# System_PMU_for_RK3399.net
KiCad netlist of a schematic drawn in Altium Designer
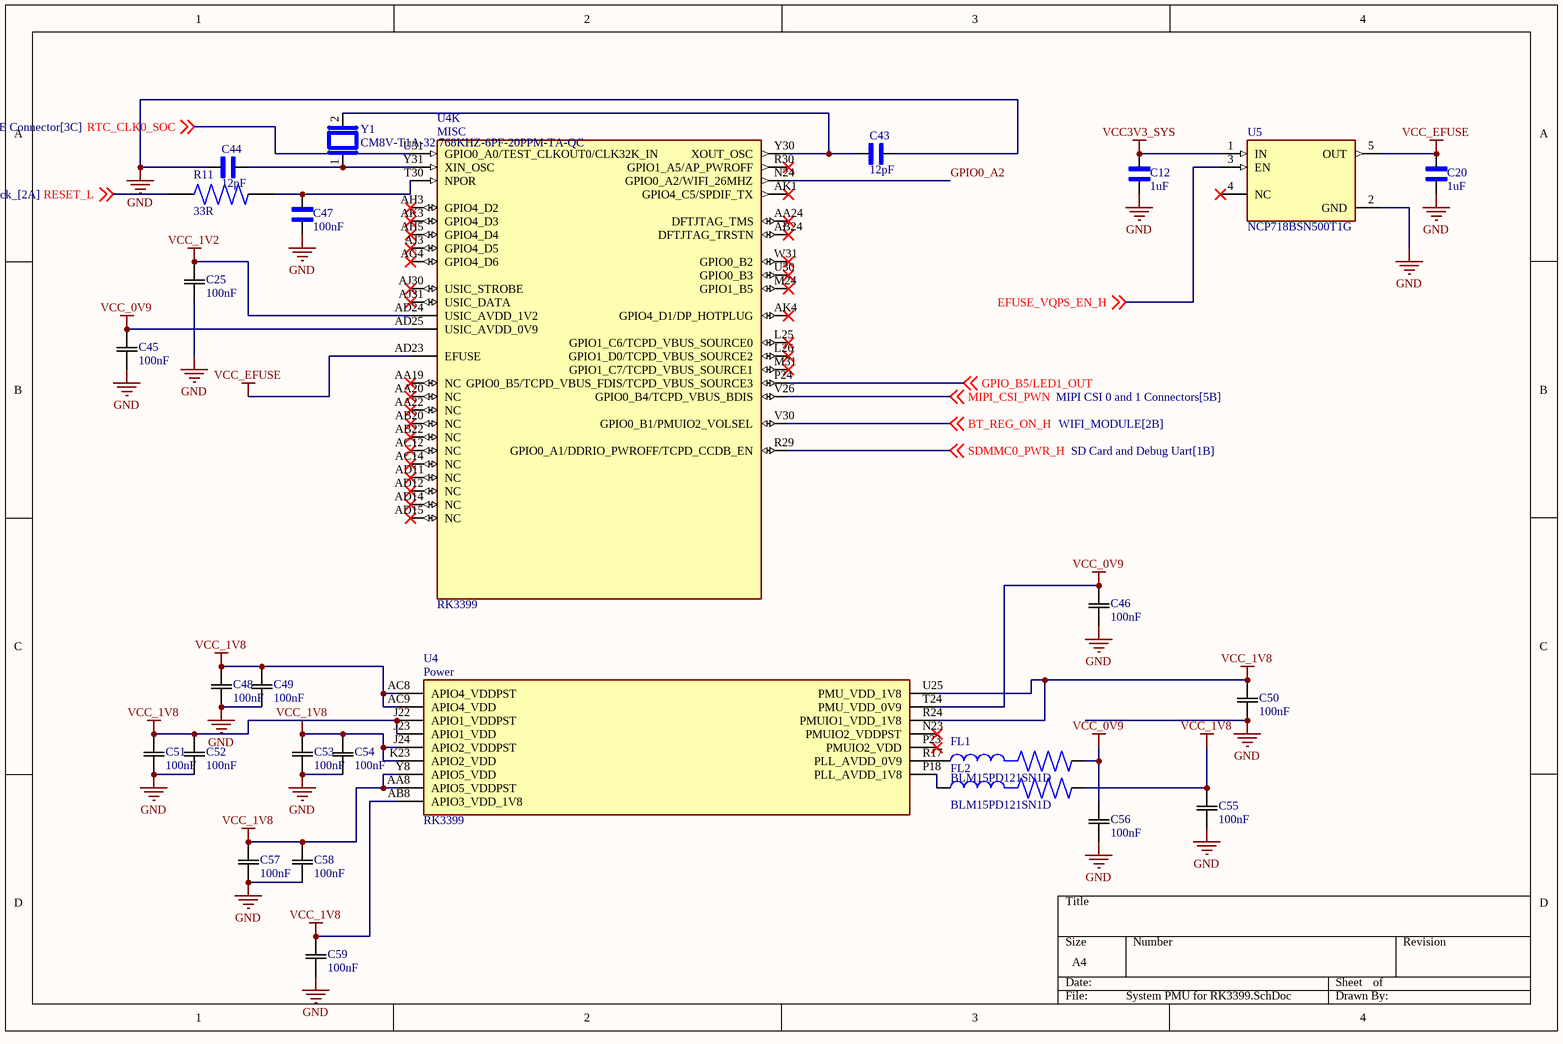
[diagram p0: System PMU for RK3399.SchDoc]

(export (version "E")
  (design (tool "Eeschema 10.0.6"))
  (components
    (comp (ref "C12")
      (value "1uF")
      (footprint "CAPC1005X56N")
      (description "1 ÂµF Â±10% 10V Ceramic Capacitor X5R 0402 (1005 Metric)")
      (fields (field (name "MF") "AVX") (field (name "MP") "0402ZD105KAT4A"))
      (libsource (lib "0402ZD105KAT4A") (part "0402ZD105KAT4A"))
    )
    (comp (ref "C20")
      (value "1uF")
      (footprint "CAPC1005X56N")
      (description "1 ÂµF Â±10% 10V Ceramic Capacitor X5R 0402 (1005 Metric)")
      (fields (field (name "MF") "AVX") (field (name "MP") "0402ZD105KAT4A"))
      (libsource (lib "0402ZD105KAT4A") (part "0402ZD105KAT4A"))
    )
    (comp (ref "C25")
      (value "100nF")
      (footprint "CAP_1005_TDK")
      (description "Description")
      (fields
        (field (name "MANUFACTURER_PART_NUMBER") "C1005X7R1H104M050BB")
        (field (name "COPYRIGHT") "Copyright (C) 2025 Ultra Librarian. All rights reserved.")
      )
      (libsource (lib "C1005X7R1H104M050BB") (part "C1005X7R1H104M050BB"))
    )
    (comp (ref "C43")
      (value "12pF")
      (footprint "CAPC1608X90")
      (description "12 pF Thin Film Capacitor 50 V 0603 (1608 Metric)")
      (fields (field (name "MF") "AVX") (field (name "MP") "06035J120FBSTR"))
      (libsource (lib "06035J120FBSTR") (part "06035J120FBSTR"))
    )
    (comp (ref "C44")
      (value "12pF")
      (footprint "CAPC0603X33N")
      (description "Cap Ceramic 12pF 25V C0G 2% Pad SMD 0201 125Â°C T/R")
      (fields (field (name "MF") "KYOCERA AVX Components") (field (name "MP") "02013A120GAT2A"))
      (libsource (lib "02013A120GAT2A") (part "02013A120GAT2A"))
    )
    (comp (ref "C45")
      (value "100nF")
      (footprint "CAP_1005_TDK")
      (description "Description")
      (fields
        (field (name "MANUFACTURER_PART_NUMBER") "C1005X7R1H104M050BB")
        (field (name "COPYRIGHT") "Copyright (C) 2025 Ultra Librarian. All rights reserved.")
      )
      (libsource (lib "C1005X7R1H104M050BB") (part "C1005X7R1H104M050BB"))
    )
    (comp (ref "C46")
      (value "100nF")
      (footprint "CAP_1005_TDK")
      (description "Description")
      (fields
        (field (name "MANUFACTURER_PART_NUMBER") "C1005X7R1H104M050BB")
        (field (name "COPYRIGHT") "Copyright (C) 2025 Ultra Librarian. All rights reserved.")
      )
      (libsource (lib "C1005X7R1H104M050BB") (part "C1005X7R1H104M050BB"))
    )
    (comp (ref "C47")
      (value "100nF")
      (footprint "CAPC2012X90N")
      (description "Capacitor: ceramic; MLCC; 100nF; 25V; X7R; Â±10%; SMD; 0805")
      (fields (field (name "MF") "Vishay Vitramon") (field (name "MP") "VJ0805Y104KXXCW1BC"))
      (libsource (lib "VJ0805Y104KXXCW1BC") (part "VJ0805Y104KXXCW1BC"))
    )
    (comp (ref "C48")
      (value "100nF")
      (footprint "CAP_1005_TDK")
      (description "Description")
      (fields
        (field (name "MANUFACTURER_PART_NUMBER") "C1005X7R1H104M050BB")
        (field (name "COPYRIGHT") "Copyright (C) 2025 Ultra Librarian. All rights reserved.")
      )
      (libsource (lib "C1005X7R1H104M050BB") (part "C1005X7R1H104M050BB"))
    )
    (comp (ref "C49")
      (value "100nF")
      (footprint "CAP_1005_TDK")
      (description "Description")
      (fields
        (field (name "MANUFACTURER_PART_NUMBER") "C1005X7R1H104M050BB")
        (field (name "COPYRIGHT") "Copyright (C) 2025 Ultra Librarian. All rights reserved.")
      )
      (libsource (lib "C1005X7R1H104M050BB") (part "C1005X7R1H104M050BB"))
    )
    (comp (ref "C50")
      (value "100nF")
      (footprint "CAP_1005_TDK")
      (description "Description")
      (fields
        (field (name "MANUFACTURER_PART_NUMBER") "C1005X7R1H104M050BB")
        (field (name "COPYRIGHT") "Copyright (C) 2025 Ultra Librarian. All rights reserved.")
      )
      (libsource (lib "C1005X7R1H104M050BB") (part "C1005X7R1H104M050BB"))
    )
    (comp (ref "C51")
      (value "100nF")
      (footprint "CAP_1005_TDK")
      (description "Description")
      (fields
        (field (name "MANUFACTURER_PART_NUMBER") "C1005X7R1H104M050BB")
        (field (name "COPYRIGHT") "Copyright (C) 2025 Ultra Librarian. All rights reserved.")
      )
      (libsource (lib "C1005X7R1H104M050BB") (part "C1005X7R1H104M050BB"))
    )
    (comp (ref "C52")
      (value "100nF")
      (footprint "CAP_1005_TDK")
      (description "Description")
      (fields
        (field (name "MANUFACTURER_PART_NUMBER") "C1005X7R1H104M050BB")
        (field (name "COPYRIGHT") "Copyright (C) 2025 Ultra Librarian. All rights reserved.")
      )
      (libsource (lib "C1005X7R1H104M050BB") (part "C1005X7R1H104M050BB"))
    )
    (comp (ref "C53")
      (value "100nF")
      (footprint "CAP_1005_TDK")
      (description "Description")
      (fields
        (field (name "MANUFACTURER_PART_NUMBER") "C1005X7R1H104M050BB")
        (field (name "COPYRIGHT") "Copyright (C) 2025 Ultra Librarian. All rights reserved.")
      )
      (libsource (lib "C1005X7R1H104M050BB") (part "C1005X7R1H104M050BB"))
    )
    (comp (ref "C54")
      (value "100nF")
      (footprint "CAP_1005_TDK")
      (description "Description")
      (fields
        (field (name "MANUFACTURER_PART_NUMBER") "C1005X7R1H104M050BB")
        (field (name "COPYRIGHT") "Copyright (C) 2025 Ultra Librarian. All rights reserved.")
      )
      (libsource (lib "C1005X7R1H104M050BB") (part "C1005X7R1H104M050BB"))
    )
    (comp (ref "C55")
      (value "100nF")
      (footprint "CAP_1005_TDK")
      (description "Description")
      (fields
        (field (name "MANUFACTURER_PART_NUMBER") "C1005X7R1H104M050BB")
        (field (name "COPYRIGHT") "Copyright (C) 2025 Ultra Librarian. All rights reserved.")
      )
      (libsource (lib "C1005X7R1H104M050BB") (part "C1005X7R1H104M050BB"))
    )
    (comp (ref "C56")
      (value "100nF")
      (footprint "CAP_1005_TDK")
      (description "Description")
      (fields
        (field (name "MANUFACTURER_PART_NUMBER") "C1005X7R1H104M050BB")
        (field (name "COPYRIGHT") "Copyright (C) 2025 Ultra Librarian. All rights reserved.")
      )
      (libsource (lib "C1005X7R1H104M050BB") (part "C1005X7R1H104M050BB"))
    )
    (comp (ref "C57")
      (value "100nF")
      (footprint "CAP_1005_TDK")
      (description "Description")
      (fields
        (field (name "MANUFACTURER_PART_NUMBER") "C1005X7R1H104M050BB")
        (field (name "COPYRIGHT") "Copyright (C) 2025 Ultra Librarian. All rights reserved.")
      )
      (libsource (lib "C1005X7R1H104M050BB") (part "C1005X7R1H104M050BB"))
    )
    (comp (ref "C58")
      (value "100nF")
      (footprint "CAP_1005_TDK")
      (description "Description")
      (fields
        (field (name "MANUFACTURER_PART_NUMBER") "C1005X7R1H104M050BB")
        (field (name "COPYRIGHT") "Copyright (C) 2025 Ultra Librarian. All rights reserved.")
      )
      (libsource (lib "C1005X7R1H104M050BB") (part "C1005X7R1H104M050BB"))
    )
    (comp (ref "C59")
      (value "100nF")
      (footprint "CAP_1005_TDK")
      (description "Description")
      (fields
        (field (name "MANUFACTURER_PART_NUMBER") "C1005X7R1H104M050BB")
        (field (name "COPYRIGHT") "Copyright (C) 2025 Ultra Librarian. All rights reserved.")
      )
      (libsource (lib "C1005X7R1H104M050BB") (part "C1005X7R1H104M050BB"))
    )
    (comp (ref "FL1")
      (value "BLM15PD121SN1D")
      (footprint "BEADC1005X55N")
      (description "120 Ohms @ 100 MHz 1 Power Line Ferrite Bead 0402 (1005 Metric) 1.3A 90mOhm")
      (fields (field (name "MF") "Murata"))
      (libsource (lib "BLM15PD121SN1D") (part "BLM15PD121SN1D"))
    )
    (comp (ref "FL2")
      (value "BLM15PD121SN1D")
      (footprint "BEADC1005X55N")
      (description "120 Ohms @ 100 MHz 1 Power Line Ferrite Bead 0402 (1005 Metric) 1.3A 90mOhm")
      (fields (field (name "MF") "Murata"))
      (libsource (lib "BLM15PD121SN1D") (part "BLM15PD121SN1D"))
    )
    (comp (ref "R11")
      (value "33R")
      (footprint "RES_ERA6AHD330V")
      (fields (field (name "MP") "ERA6AHD330V"))
      (libsource (lib "ERA6AHD330V") (part "ERA6AHD330V"))
    )
    (comp (ref "U4")
      (value "RK3399")
      (footprint "BGA828C65P31X31_2100X2100X161N")
      (description "RK3399 ROCK Pi 4 Model A 2GB - ARMÂ® CortexÂ®-A53, CortexÂ®-A72 MPU Embedded Evaluation Board")
      (fields (field (name "MF") "Rockchip"))
      (libsource (lib "RK3399") (part "RK3399"))
    )
    (comp (ref "U5")
      (value "NCP718BSN500T1G")
      (footprint "SOT95P280X100-5N")
      (description "Linear Voltage Regulator IC Positive Fixed 1 Output 300mA TSOT-23-5")
      (fields (field (name "MF") "ON Semiconductor"))
      (libsource (lib "NCP718BSN500T1G") (part "NCP718BSN500T1G"))
    )
    (comp (ref "Y1")
      (value "CM8V-T1A-32.768KHZ-6PF-20PPM-TA-QC")
      (footprint "XTAL_CM8V-T1A-32.768KHZ-6PF-20PPM-TA-QC")
      (description "Tuning Fork Crystal 32.768kHz in SMD 1.2 x 2.0mm package")
      (fields (field (name "MF") "Micro Crystal") (field (name "MP") "CM8V-T1A-32.768kHz-6pF-20PPM-TA-QC"))
      (libsource (lib "CM8V-T1A-32.768KHZ-6PF-20PPM-TA-QC") (part "CM8V-T1A-32.768KHZ-6PF-20PPM-TA-QC"))
    )
  )
  (nets
    (net (code "1") (name "/GPIO0_A2") (class "Default")
      (node (ref "U4") (pin "N24") (pinfunction "GPIO0_A2/WIFI_26MHZ_N24") (pintype "output"))
    )
    (net (code "2") (name "BT_REG_ON_H") (class "Default")
      (node (ref "U4") (pin "V30") (pinfunction "GPIO0_B1/PMUIO2_VOLSEL_V30") (pintype "bidirectional"))
    )
    (net (code "3") (name "EFUSE_VQPS_EN_H") (class "Default")
      (node (ref "U5") (pin "3") (pinfunction "EN_3") (pintype "input"))
    )
    (net (code "4") (name "GND") (class "Default")
      (node (ref "C12") (pin "2") (pinfunction "2_2") (pintype "passive"))
      (node (ref "C20") (pin "2") (pinfunction "2_2") (pintype "passive"))
      (node (ref "C25") (pin "2") (pinfunction "2_2") (pintype "passive"))
      (node (ref "C43") (pin "1") (pinfunction "1_1") (pintype "passive"))
      (node (ref "C44") (pin "1") (pinfunction "1_1") (pintype "passive"))
      (node (ref "C45") (pin "2") (pinfunction "2_2") (pintype "passive"))
      (node (ref "C46") (pin "2") (pinfunction "2_2") (pintype "passive"))
      (node (ref "C47") (pin "2") (pinfunction "2_2") (pintype "passive"))
      (node (ref "C48") (pin "2") (pinfunction "2_2") (pintype "passive"))
      (node (ref "C49") (pin "2") (pinfunction "2_2") (pintype "passive"))
      (node (ref "C50") (pin "2") (pinfunction "2_2") (pintype "passive"))
      (node (ref "C51") (pin "2") (pinfunction "2_2") (pintype "passive"))
      (node (ref "C52") (pin "2") (pinfunction "2_2") (pintype "passive"))
      (node (ref "C53") (pin "2") (pinfunction "2_2") (pintype "passive"))
      (node (ref "C54") (pin "1") (pinfunction "1_1") (pintype "passive"))
      (node (ref "C55") (pin "2") (pinfunction "2_2") (pintype "passive"))
      (node (ref "C56") (pin "2") (pinfunction "2_2") (pintype "passive"))
      (node (ref "C57") (pin "2") (pinfunction "2_2") (pintype "passive"))
      (node (ref "C58") (pin "2") (pinfunction "2_2") (pintype "passive"))
      (node (ref "C59") (pin "2") (pinfunction "2_2") (pintype "passive"))
      (node (ref "U5") (pin "2") (pinfunction "GND_2") (pintype "power_in"))
    )
    (net (code "5") (name "GPIO_B5{slash}LED1_OUT") (class "Default")
      (node (ref "U4") (pin "P24") (pinfunction "GPIO0_B5/TCPD_VBUS_FDIS/TCPD_VBUS_SOURCE3_P24") (pintype "bidirectional"))
    )
    (net (code "6") (name "MIPI_CSI_PWN") (class "Default")
      (node (ref "U4") (pin "V26") (pinfunction "GPIO0_B4/TCPD_VBUS_BDIS_V26") (pintype "bidirectional"))
    )
    (net (code "7") (name "Net-(U4AC-PLL_AVDD_0V9)") (class "Default")
      (node (ref "FL1") (pin "1") (pinfunction "1_1") (pintype "passive"))
      (node (ref "U4") (pin "R17") (pinfunction "PLL_AVDD_0V9_R17") (pintype "power_in"))
    )
    (net (code "8") (name "Net-(U4AC-PLL_AVDD_1V8)") (class "Default")
      (node (ref "FL2") (pin "1") (pinfunction "1_1") (pintype "passive"))
      (node (ref "U4") (pin "P18") (pinfunction "PLL_AVDD_1V8_P18") (pintype "power_in"))
    )
    (net (code "9") (name "Net-(U4K-NPOR)") (class "Default")
      (node (ref "C47") (pin "1") (pinfunction "1_1") (pintype "passive"))
      (node (ref "R11") (pin "2") (pinfunction "2_2") (pintype "passive"))
      (node (ref "U4") (pin "T30") (pinfunction "NPOR_T30") (pintype "input"))
    )
    (net (code "10") (name "Net-(U4K-XIN_OSC)") (class "Default")
      (node (ref "C44") (pin "2") (pinfunction "2_2") (pintype "passive"))
      (node (ref "U4") (pin "Y31") (pinfunction "XIN_OSC_Y31") (pintype "input"))
      (node (ref "Y1") (pin "1") (pinfunction "1_1") (pintype "passive"))
    )
    (net (code "11") (name "Net-(U4K-XOUT_OSC)") (class "Default")
      (node (ref "C43") (pin "2") (pinfunction "2_2") (pintype "passive"))
      (node (ref "U4") (pin "Y30") (pinfunction "XOUT_OSC_Y30") (pintype "output"))
      (node (ref "Y1") (pin "2") (pinfunction "2_2") (pintype "passive"))
    )
    (net (code "12") (name "RESET_L") (class "Default")
      (node (ref "R11") (pin "1") (pinfunction "1_1") (pintype "passive"))
    )
    (net (code "13") (name "RTC_CLK0_SOC") (class "Default")
      (node (ref "U4") (pin "U31") (pinfunction "GPIO0_A0/TEST_CLKOUT0/CLK32K_IN_U31") (pintype "input"))
    )
    (net (code "14") (name "SDMMC0_PWR_H") (class "Default")
      (node (ref "U4") (pin "R29") (pinfunction "GPIO0_A1/DDRIO_PWROFF/TCPD_CCDB_EN_R29") (pintype "bidirectional"))
    )
    (net (code "15") (name "VCC3V3_SYS") (class "Default")
      (node (ref "C12") (pin "1") (pinfunction "1_1") (pintype "passive"))
      (node (ref "U5") (pin "1") (pinfunction "IN_1") (pintype "input"))
    )
    (net (code "16") (name "VCC_0V9") (class "Default")
      (node (ref "C45") (pin "1") (pinfunction "1_1") (pintype "passive"))
      (node (ref "C46") (pin "1") (pinfunction "1_1") (pintype "passive"))
      (node (ref "C56") (pin "1") (pinfunction "1_1") (pintype "passive"))
      (node (ref "FL1") (pin "2") (pinfunction "2_2") (pintype "passive"))
      (node (ref "U4") (pin "AD25") (pinfunction "USIC_AVDD_0V9_AD25") (pintype "power_in"))
      (node (ref "U4") (pin "T24") (pinfunction "PMU_VDD_0V9_T24") (pintype "power_in"))
    )
    (net (code "17") (name "VCC_1V2") (class "Default")
      (node (ref "C25") (pin "1") (pinfunction "1_1") (pintype "passive"))
      (node (ref "U4") (pin "AD24") (pinfunction "USIC_AVDD_1V2_AD24") (pintype "power_in"))
    )
    (net (code "18") (name "VCC_1V8") (class "Default")
      (node (ref "C48") (pin "1") (pinfunction "1_1") (pintype "passive"))
      (node (ref "C49") (pin "1") (pinfunction "1_1") (pintype "passive"))
      (node (ref "C50") (pin "1") (pinfunction "1_1") (pintype "passive"))
      (node (ref "C51") (pin "1") (pinfunction "1_1") (pintype "passive"))
      (node (ref "C52") (pin "1") (pinfunction "1_1") (pintype "passive"))
      (node (ref "C53") (pin "1") (pinfunction "1_1") (pintype "passive"))
      (node (ref "C54") (pin "2") (pinfunction "2_2") (pintype "passive"))
      (node (ref "C55") (pin "1") (pinfunction "1_1") (pintype "passive"))
      (node (ref "C57") (pin "1") (pinfunction "1_1") (pintype "passive"))
      (node (ref "C58") (pin "1") (pinfunction "1_1") (pintype "passive"))
      (node (ref "C59") (pin "1") (pinfunction "1_1") (pintype "passive"))
      (node (ref "FL2") (pin "2") (pinfunction "2_2") (pintype "passive"))
      (node (ref "U4") (pin "AA8") (pinfunction "APIO5_VDDPST_AA8") (pintype "power_in"))
      (node (ref "U4") (pin "AB8") (pinfunction "APIO3_VDD_1V8_AB8") (pintype "power_in"))
      (node (ref "U4") (pin "AC8") (pinfunction "APIO4_VDDPST_AC8") (pintype "power_in"))
      (node (ref "U4") (pin "AC9") (pinfunction "APIO4_VDD_AC9") (pintype "power_in"))
      (node (ref "U4") (pin "J22") (pinfunction "APIO1_VDDPST_J22") (pintype "power_in"))
      (node (ref "U4") (pin "J23") (pinfunction "APIO1_VDD_J23") (pintype "power_in"))
      (node (ref "U4") (pin "J24") (pinfunction "APIO2_VDDPST_J24") (pintype "power_in"))
      (node (ref "U4") (pin "K23") (pinfunction "APIO2_VDD_K23") (pintype "power_in"))
      (node (ref "U4") (pin "R24") (pinfunction "PMUIO1_VDD_1V8_R24") (pintype "power_in"))
      (node (ref "U4") (pin "U25") (pinfunction "PMU_VDD_1V8_U25") (pintype "power_in"))
      (node (ref "U4") (pin "Y8") (pinfunction "APIO5_VDD_Y8") (pintype "power_in"))
    )
    (net (code "19") (name "VCC_EFUSE") (class "Default")
      (node (ref "C20") (pin "1") (pinfunction "1_1") (pintype "passive"))
      (node (ref "U4") (pin "AD23") (pinfunction "EFUSE_AD23") (pintype "passive"))
      (node (ref "U5") (pin "5") (pinfunction "OUT_5") (pintype "output"))
    )
    (net (code "20") (name "unconnected-(U4AC-PMUIO2_VDD-PadP23)") (class "Default")
      (node (ref "U4") (pin "P23") (pinfunction "PMUIO2_VDD_P23") (pintype "power_in+no_connect"))
    )
    (net (code "21") (name "unconnected-(U4AC-PMUIO2_VDDPST-PadN23)") (class "Default")
      (node (ref "U4") (pin "N23") (pinfunction "PMUIO2_VDDPST_N23") (pintype "power_in+no_connect"))
    )
    (net (code "22") (name "unconnected-(U4K-DFTJTAG_TMS-PadAA24)") (class "Default")
      (node (ref "U4") (pin "AA24") (pinfunction "DFTJTAG_TMS_AA24") (pintype "bidirectional+no_connect"))
    )
    (net (code "23") (name "unconnected-(U4K-DFTJTAG_TRSTN-PadAB24)") (class "Default")
      (node (ref "U4") (pin "AB24") (pinfunction "DFTJTAG_TRSTN_AB24") (pintype "bidirectional+no_connect"))
    )
    (net (code "24") (name "unconnected-(U4K-GPIO0_B2-PadW31)") (class "Default")
      (node (ref "U4") (pin "W31") (pinfunction "GPIO0_B2_W31") (pintype "bidirectional+no_connect"))
    )
    (net (code "25") (name "unconnected-(U4K-GPIO0_B3-PadU30)") (class "Default")
      (node (ref "U4") (pin "U30") (pinfunction "GPIO0_B3_U30") (pintype "bidirectional+no_connect"))
    )
    (net (code "26") (name "unconnected-(U4K-GPIO1_A5{slash}AP_PWROFF-PadR30)") (class "Default")
      (node (ref "U4") (pin "R30") (pinfunction "GPIO1_A5/AP_PWROFF_R30") (pintype "output+no_connect"))
    )
    (net (code "27") (name "unconnected-(U4K-GPIO1_B5-PadM24)") (class "Default")
      (node (ref "U4") (pin "M24") (pinfunction "GPIO1_B5_M24") (pintype "bidirectional+no_connect"))
    )
    (net (code "28") (name "unconnected-(U4K-GPIO1_C6{slash}TCPD_VBUS_SOURCE0-PadL25)") (class "Default")
      (node (ref "U4") (pin "L25") (pinfunction "GPIO1_C6/TCPD_VBUS_SOURCE0_L25") (pintype "bidirectional+no_connect"))
    )
    (net (code "29") (name "unconnected-(U4K-GPIO1_C7{slash}TCPD_VBUS_SOURCE1-PadM31)") (class "Default")
      (node (ref "U4") (pin "M31") (pinfunction "GPIO1_C7/TCPD_VBUS_SOURCE1_M31") (pintype "bidirectional+no_connect"))
    )
    (net (code "30") (name "unconnected-(U4K-GPIO1_D0{slash}TCPD_VBUS_SOURCE2-PadL26)") (class "Default")
      (node (ref "U4") (pin "L26") (pinfunction "GPIO1_D0/TCPD_VBUS_SOURCE2_L26") (pintype "bidirectional+no_connect"))
    )
    (net (code "31") (name "unconnected-(U4K-GPIO4_C5{slash}SPDIF_TX-PadAK1)") (class "Default")
      (node (ref "U4") (pin "AK1") (pinfunction "GPIO4_C5/SPDIF_TX_AK1") (pintype "output+no_connect"))
    )
    (net (code "32") (name "unconnected-(U4K-GPIO4_D1{slash}DP_HOTPLUG-PadAK4)") (class "Default")
      (node (ref "U4") (pin "AK4") (pinfunction "GPIO4_D1/DP_HOTPLUG_AK4") (pintype "bidirectional+no_connect"))
    )
    (net (code "33") (name "unconnected-(U4K-GPIO4_D2-PadAH3)") (class "Default")
      (node (ref "U4") (pin "AH3") (pinfunction "GPIO4_D2_AH3") (pintype "bidirectional+no_connect"))
    )
    (net (code "34") (name "unconnected-(U4K-GPIO4_D3-PadAK3)") (class "Default")
      (node (ref "U4") (pin "AK3") (pinfunction "GPIO4_D3_AK3") (pintype "bidirectional+no_connect"))
    )
    (net (code "35") (name "unconnected-(U4K-GPIO4_D4-PadAH5)") (class "Default")
      (node (ref "U4") (pin "AH5") (pinfunction "GPIO4_D4_AH5") (pintype "bidirectional+no_connect"))
    )
    (net (code "36") (name "unconnected-(U4K-GPIO4_D5-PadAJ3)") (class "Default")
      (node (ref "U4") (pin "AJ3") (pinfunction "GPIO4_D5_AJ3") (pintype "bidirectional+no_connect"))
    )
    (net (code "37") (name "unconnected-(U4K-GPIO4_D6-PadAG4)") (class "Default")
      (node (ref "U4") (pin "AG4") (pinfunction "GPIO4_D6_AG4") (pintype "bidirectional+no_connect"))
    )
    (net (code "38") (name "unconnected-(U4K-NC-PadAA19)") (class "Default")
      (node (ref "U4") (pin "AA19") (pinfunction "NC_AA19") (pintype "bidirectional+no_connect"))
    )
    (net (code "39") (name "unconnected-(U4K-NC-PadAA20)") (class "Default")
      (node (ref "U4") (pin "AA20") (pinfunction "NC_AA20") (pintype "bidirectional+no_connect"))
    )
    (net (code "40") (name "unconnected-(U4K-NC-PadAA22)") (class "Default")
      (node (ref "U4") (pin "AA22") (pinfunction "NC_AA22") (pintype "bidirectional+no_connect"))
    )
    (net (code "41") (name "unconnected-(U4K-NC-PadAB20)") (class "Default")
      (node (ref "U4") (pin "AB20") (pinfunction "NC_AB20") (pintype "bidirectional+no_connect"))
    )
    (net (code "42") (name "unconnected-(U4K-NC-PadAB22)") (class "Default")
      (node (ref "U4") (pin "AB22") (pinfunction "NC_AB22") (pintype "bidirectional+no_connect"))
    )
    (net (code "43") (name "unconnected-(U4K-NC-PadAC12)") (class "Default")
      (node (ref "U4") (pin "AC12") (pinfunction "NC_AC12") (pintype "bidirectional+no_connect"))
    )
    (net (code "44") (name "unconnected-(U4K-NC-PadAC14)") (class "Default")
      (node (ref "U4") (pin "AC14") (pinfunction "NC_AC14") (pintype "bidirectional+no_connect"))
    )
    (net (code "45") (name "unconnected-(U4K-NC-PadAD11)") (class "Default")
      (node (ref "U4") (pin "AD11") (pinfunction "NC_AD11") (pintype "bidirectional+no_connect"))
    )
    (net (code "46") (name "unconnected-(U4K-NC-PadAD12)") (class "Default")
      (node (ref "U4") (pin "AD12") (pinfunction "NC_AD12") (pintype "bidirectional+no_connect"))
    )
    (net (code "47") (name "unconnected-(U4K-NC-PadAD14)") (class "Default")
      (node (ref "U4") (pin "AD14") (pinfunction "NC_AD14") (pintype "bidirectional+no_connect"))
    )
    (net (code "48") (name "unconnected-(U4K-NC-PadAD15)") (class "Default")
      (node (ref "U4") (pin "AD15") (pinfunction "NC_AD15") (pintype "bidirectional+no_connect"))
    )
    (net (code "49") (name "unconnected-(U4K-USIC_DATA-PadAJ31)") (class "Default")
      (node (ref "U4") (pin "AJ31") (pinfunction "USIC_DATA_AJ31") (pintype "bidirectional+no_connect"))
    )
    (net (code "50") (name "unconnected-(U4K-USIC_STROBE-PadAJ30)") (class "Default")
      (node (ref "U4") (pin "AJ30") (pinfunction "USIC_STROBE_AJ30") (pintype "bidirectional+no_connect"))
    )
    (net (code "51") (name "unconnected-(U5-NC-Pad4)") (class "Default")
      (node (ref "U5") (pin "4") (pinfunction "NC_4") (pintype "passive+no_connect"))
    )
  )
)
